# board.net
KiCad netlist of a schematic drawn in EAGLE
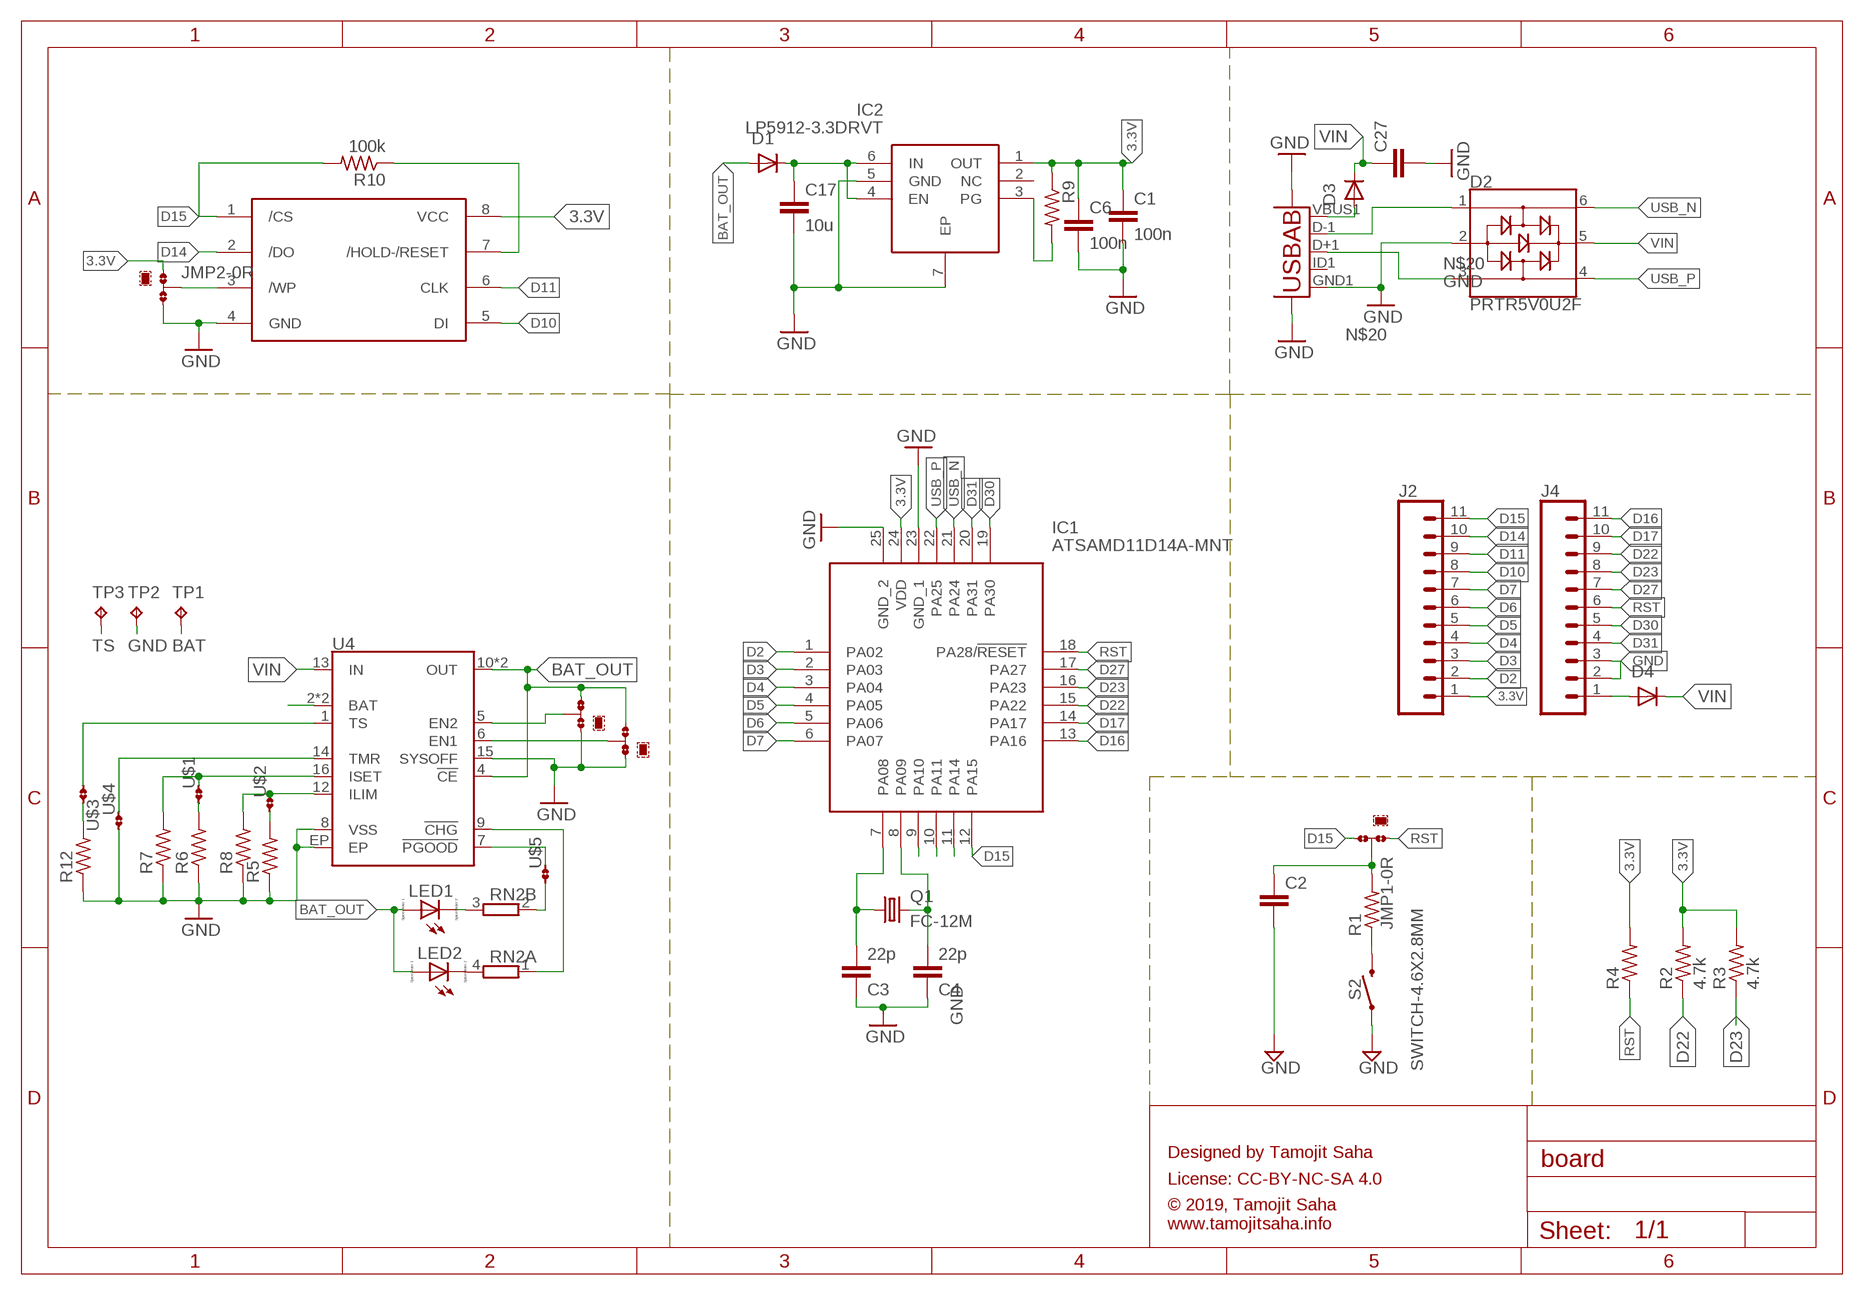
[diagram p0: schematic, sheet 1]

(export (version "E")
  (design (tool "Eeschema 10.0.6"))
  (components
    (comp (ref "C1")
      (value "100n")
      (footprint "eagle-import:C0402")
      (libsource (lib "eagle-import") (part "C-EUC0402"))
    )
    (comp (ref "C2")
      (value "C-EUC0402")
      (footprint "eagle-import:C0402")
      (libsource (lib "eagle-import") (part "C-EUC0402"))
    )
    (comp (ref "C3")
      (value "22p")
      (footprint "eagle-import:C0402")
      (libsource (lib "eagle-import") (part "C-EUC0402"))
    )
    (comp (ref "C4")
      (value "22p")
      (footprint "eagle-import:C0402")
      (libsource (lib "eagle-import") (part "C-EUC0402"))
    )
    (comp (ref "C6")
      (value "100n")
      (footprint "eagle-import:C0402")
      (libsource (lib "eagle-import") (part "C-EUC0402"))
    )
    (comp (ref "C17")
      (value "10u")
      (footprint "eagle-import:C0603")
      (libsource (lib "eagle-import") (part "C-EUC0603"))
    )
    (comp (ref "C27")
      (value "C-EUC0603")
      (footprint "eagle-import:C0603")
      (libsource (lib "eagle-import") (part "C-EUC0603"))
    )
    (comp (ref "D1")
      (value "PMEG1030")
      (footprint "eagle-import:SOD323(F)")
      (fields (field (name "MF") "NXP Semiconductors") (field (name "MP") "BAS21J"))
      (libsource (lib "eagle-import") (part "PMEG1030"))
    )
    (comp (ref "D2")
      (value "PRTR5V0U2F")
      (footprint "eagle-import:SOT886")
      (libsource (lib "eagle-import") (part "PRTR5V0U2F"))
    )
    (comp (ref "D3")
      (value "PMEG1030")
      (footprint "eagle-import:SOD323(F)")
      (fields (field (name "MF") "NXP Semiconductors") (field (name "MP") "BAS21J"))
      (libsource (lib "eagle-import") (part "PMEG1030"))
    )
    (comp (ref "D4")
      (value "PMEG1030")
      (footprint "eagle-import:SOD323(F)")
      (fields (field (name "MF") "NXP Semiconductors") (field (name "MP") "BAS21J"))
      (libsource (lib "eagle-import") (part "PMEG1030"))
    )
    (comp (ref "EEPROM1")
      (value "W25Q128JVPIQ")
      (footprint "eagle-import:SON127P600X500X80-9N")
      (libsource (lib "eagle-import") (part "W25Q128JVPIQ"))
    )
    (comp (ref "IC1")
      (value "ATSAMD11D14A-MNT")
      (footprint "eagle-import:QFN50P400X400X90-25N")
      (fields (field (name "MOUSER_PART_NUMBER") "556-ATSAMD11D14A-MNT"))
      (libsource (lib "eagle-import") (part "ATSAMD11D14A-MNT"))
    )
    (comp (ref "IC2")
      (value "LP5912-3.3DRVT")
      (footprint "eagle-import:WSON-6")
      (fields (field (name "MOUSER_PART_NUMBER") "595-LP5912-3.3DRVT"))
      (libsource (lib "eagle-import") (part "LP5912-3.3DRVT"))
    )
    (comp (ref "J2")
      (value "CONN_111X11_NO_SILK")
      (footprint "eagle-import:1X11_NO_SILK")
      (libsource (lib "eagle-import") (part "CONN_111X11_NO_SILK"))
    )
    (comp (ref "J4")
      (value "CONN_111X11_NO_SILK")
      (footprint "eagle-import:1X11_NO_SILK")
      (libsource (lib "eagle-import") (part "CONN_111X11_NO_SILK"))
    )
    (comp (ref "JMP1")
      (value "0R-JUMPA")
      (footprint "eagle-import:A0R-JMP")
      (libsource (lib "eagle-import") (part "0R-JUMPA"))
    )
    (comp (ref "JMP2")
      (value "0R-JUMPA")
      (footprint "eagle-import:A0R-JMP")
      (libsource (lib "eagle-import") (part "0R-JUMPA"))
    )
    (comp (ref "JMP3")
      (value "0R-JUMPA")
      (footprint "eagle-import:A0R-JMP")
      (libsource (lib "eagle-import") (part "0R-JUMPA"))
    )
    (comp (ref "JMP4")
      (value "0R-JUMPA")
      (footprint "eagle-import:A0R-JMP")
      (libsource (lib "eagle-import") (part "0R-JUMPA"))
    )
    (comp (ref "LED1")
      (value "LED_ESML0603")
      (footprint "eagle-import:LED_SML0603")
      (libsource (lib "eagle-import") (part "LED_ESML0603"))
    )
    (comp (ref "LED2")
      (value "LED_ESML0603")
      (footprint "eagle-import:LED_SML0603")
      (libsource (lib "eagle-import") (part "LED_ESML0603"))
    )
    (comp (ref "Q1")
      (value "FC-12M")
      (footprint "eagle-import:FC-12M")
      (libsource (lib "eagle-import") (part "FC-12M"))
    )
    (comp (ref "R1")
      (value "R-US_R0402")
      (footprint "eagle-import:R0402")
      (libsource (lib "eagle-import") (part "R-US_R0402"))
    )
    (comp (ref "R2")
      (value "4.7k")
      (footprint "eagle-import:R0402")
      (libsource (lib "eagle-import") (part "R-US_R0402"))
    )
    (comp (ref "R3")
      (value "4.7k")
      (footprint "eagle-import:R0402")
      (libsource (lib "eagle-import") (part "R-US_R0402"))
    )
    (comp (ref "R4")
      (value "R-US_R0402")
      (footprint "eagle-import:R0402")
      (libsource (lib "eagle-import") (part "R-US_R0402"))
    )
    (comp (ref "R5")
      (value "R-US_R0402")
      (footprint "eagle-import:R0402")
      (libsource (lib "eagle-import") (part "R-US_R0402"))
    )
    (comp (ref "R6")
      (value "R-US_R0402")
      (footprint "eagle-import:R0402")
      (libsource (lib "eagle-import") (part "R-US_R0402"))
    )
    (comp (ref "R7")
      (value "R-US_R0402")
      (footprint "eagle-import:R0402")
      (libsource (lib "eagle-import") (part "R-US_R0402"))
    )
    (comp (ref "R8")
      (value "R-US_R0402")
      (footprint "eagle-import:R0402")
      (libsource (lib "eagle-import") (part "R-US_R0402"))
    )
    (comp (ref "R9")
      (value "R-US_R0402")
      (footprint "eagle-import:R0402")
      (libsource (lib "eagle-import") (part "R-US_R0402"))
    )
    (comp (ref "R10")
      (value "100k")
      (footprint "eagle-import:R0402")
      (libsource (lib "eagle-import") (part "R-US_R0402"))
    )
    (comp (ref "R12")
      (value "R-US_R0402")
      (footprint "eagle-import:R0402")
      (libsource (lib "eagle-import") (part "R-US_R0402"))
    )
    (comp (ref "RN2")
      (value "2R-NEXB24V")
      (footprint "eagle-import:EXB24V")
      (libsource (lib "eagle-import") (part "2R-NEXB24V"))
    )
    (comp (ref "S2")
      (value "SWITCH-4.6X2.8MM")
      (footprint "eagle-import:TACTILE_SWITCH_SMD_4.6X2.8MM")
      (libsource (lib "eagle-import") (part "MOMENTARY-SWITCH-SPST-SMD-4.6X2.8MM"))
    )
    (comp (ref "TP1")
      (value "TPB1,27")
      (footprint "eagle-import:B1,27")
      (libsource (lib "eagle-import") (part "TPB1,27"))
    )
    (comp (ref "TP2")
      (value "TPB1,27")
      (footprint "eagle-import:B1,27")
      (libsource (lib "eagle-import") (part "TPB1,27"))
    )
    (comp (ref "TP3")
      (value "TPB1,27")
      (footprint "eagle-import:B1,27")
      (libsource (lib "eagle-import") (part "TPB1,27"))
    )
    (comp (ref "U$1")
      (value "JMP-2-NO-0402")
      (footprint "eagle-import:JMP-2-NO-0402")
      (libsource (lib "eagle-import") (part "JMP-2-NO-0402"))
    )
    (comp (ref "U$2")
      (value "JMP-2-NO-0402")
      (footprint "eagle-import:JMP-2-NO-0402")
      (libsource (lib "eagle-import") (part "JMP-2-NO-0402"))
    )
    (comp (ref "U$3")
      (value "JMP-2-NO-0402")
      (footprint "eagle-import:JMP-2-NO-0402")
      (libsource (lib "eagle-import") (part "JMP-2-NO-0402"))
    )
    (comp (ref "U$4")
      (value "JMP-2-NO-0402")
      (footprint "eagle-import:JMP-2-NO-0402")
      (libsource (lib "eagle-import") (part "JMP-2-NO-0402"))
    )
    (comp (ref "U$5")
      (value "JMP-2-NO-0402")
      (footprint "eagle-import:JMP-2-NO-0402")
      (libsource (lib "eagle-import") (part "JMP-2-NO-0402"))
    )
    (comp (ref "U3")
      (value "USB\"\"")
      (footprint "eagle-import:USB-MICRO-SMD")
      (libsource (lib "eagle-import") (part "USB{dblquote}{dblquote}"))
    )
    (comp (ref "U4")
      (value "BQ24075")
      (footprint "eagle-import:PVQFN-N16")
      (libsource (lib "eagle-import") (part "BQ24075"))
    )
  )
  (nets
    (net (code "1") (name "/BAT") (class "Default")
      (node (ref "TP1") (pin "TP") (pinfunction "TP_TP") (pintype "input"))
      (node (ref "U4") (pin "2") (pinfunction "BAT_2") (pintype "bidirectional"))
      (node (ref "U4") (pin "3") (pinfunction "BAT_3") (pintype "bidirectional"))
    )
    (net (code "2") (name "/N$20") (class "Default")
      (node (ref "D3") (pin "2") (pinfunction "A_2") (pintype "passive"))
      (node (ref "U3") (pin "VBUS1") (pinfunction "VBUS_VBUS1") (pintype "bidirectional"))
    )
    (net (code "3") (name "/TS") (class "Default")
      (node (ref "TP3") (pin "TP") (pinfunction "TP_TP") (pintype "input"))
      (node (ref "U$3") (pin "1") (pinfunction "1_1") (pintype "passive"))
      (node (ref "U4") (pin "1") (pinfunction "TS_1") (pintype "bidirectional"))
    )
    (net (code "4") (name "3.3V") (class "Default")
      (node (ref "C1") (pin "1") (pinfunction "1_1") (pintype "passive"))
      (node (ref "C6") (pin "1") (pinfunction "1_1") (pintype "passive"))
      (node (ref "EEPROM1") (pin "8") (pinfunction "VCC_8") (pintype "bidirectional"))
      (node (ref "IC1") (pin "24") (pinfunction "VDD_24") (pintype "bidirectional"))
      (node (ref "IC2") (pin "1") (pinfunction "OUT_1") (pintype "bidirectional"))
      (node (ref "J2") (pin "1") (pinfunction "1_1") (pintype "passive"))
      (node (ref "JMP2") (pin "1") (pinfunction "1_1") (pintype "passive"))
      (node (ref "R2") (pin "2") (pinfunction "2_2") (pintype "passive"))
      (node (ref "R3") (pin "2") (pinfunction "2_2") (pintype "passive"))
      (node (ref "R4") (pin "2") (pinfunction "2_2") (pintype "passive"))
      (node (ref "R9") (pin "1") (pinfunction "1_1") (pintype "passive"))
    )
    (net (code "5") (name "BAT_OUT") (class "Default")
      (node (ref "D1") (pin "2") (pinfunction "A_2") (pintype "passive"))
      (node (ref "JMP3") (pin "3") (pinfunction "3_3") (pintype "passive"))
      (node (ref "JMP4") (pin "3") (pinfunction "3_3") (pintype "passive"))
      (node (ref "LED1") (pin "A") (pinfunction "A_A") (pintype "passive"))
      (node (ref "LED2") (pin "A") (pinfunction "A_A") (pintype "passive"))
      (node (ref "U4") (pin "10") (pinfunction "OUT_10") (pintype "bidirectional"))
      (node (ref "U4") (pin "11") (pinfunction "OUT_11") (pintype "bidirectional"))
      (node (ref "U4") (pin "4") (pinfunction "~{CE}_4") (pintype "bidirectional"))
    )
    (net (code "6") (name "D2") (class "Default")
      (node (ref "IC1") (pin "1") (pinfunction "PA02_1") (pintype "bidirectional"))
      (node (ref "J2") (pin "2") (pinfunction "2_2") (pintype "passive"))
    )
    (net (code "7") (name "D3") (class "Default")
      (node (ref "IC1") (pin "2") (pinfunction "PA03_2") (pintype "bidirectional"))
      (node (ref "J2") (pin "3") (pinfunction "3_3") (pintype "passive"))
    )
    (net (code "8") (name "D4") (class "Default")
      (node (ref "IC1") (pin "3") (pinfunction "PA04_3") (pintype "bidirectional"))
      (node (ref "J2") (pin "4") (pinfunction "4_4") (pintype "passive"))
    )
    (net (code "9") (name "D5") (class "Default")
      (node (ref "IC1") (pin "4") (pinfunction "PA05_4") (pintype "bidirectional"))
      (node (ref "J2") (pin "5") (pinfunction "5_5") (pintype "passive"))
    )
    (net (code "10") (name "D6") (class "Default")
      (node (ref "IC1") (pin "5") (pinfunction "PA06_5") (pintype "bidirectional"))
      (node (ref "J2") (pin "6") (pinfunction "6_6") (pintype "passive"))
    )
    (net (code "11") (name "D7") (class "Default")
      (node (ref "IC1") (pin "6") (pinfunction "PA07_6") (pintype "bidirectional"))
      (node (ref "J2") (pin "7") (pinfunction "7_7") (pintype "passive"))
    )
    (net (code "12") (name "D10") (class "Default")
      (node (ref "EEPROM1") (pin "5") (pinfunction "DI_5") (pintype "bidirectional"))
      (node (ref "IC1") (pin "9") (pinfunction "PA10_9") (pintype "bidirectional"))
      (node (ref "J2") (pin "8") (pinfunction "8_8") (pintype "passive"))
    )
    (net (code "13") (name "D11") (class "Default")
      (node (ref "EEPROM1") (pin "6") (pinfunction "CLK_6") (pintype "bidirectional"))
      (node (ref "IC1") (pin "10") (pinfunction "PA11_10") (pintype "bidirectional"))
      (node (ref "J2") (pin "9") (pinfunction "9_9") (pintype "passive"))
    )
    (net (code "14") (name "D14") (class "Default")
      (node (ref "EEPROM1") (pin "2") (pinfunction "/DO_2") (pintype "bidirectional"))
      (node (ref "IC1") (pin "11") (pinfunction "PA14_11") (pintype "bidirectional"))
      (node (ref "J2") (pin "10") (pinfunction "10_10") (pintype "passive"))
    )
    (net (code "15") (name "D15") (class "Default")
      (node (ref "EEPROM1") (pin "1") (pinfunction "/CS_1") (pintype "bidirectional"))
      (node (ref "IC1") (pin "12") (pinfunction "PA15_12") (pintype "bidirectional"))
      (node (ref "J2") (pin "11") (pinfunction "11_11") (pintype "passive"))
      (node (ref "JMP1") (pin "3") (pinfunction "3_3") (pintype "passive"))
      (node (ref "R10") (pin "2") (pinfunction "2_2") (pintype "passive"))
    )
    (net (code "16") (name "D16") (class "Default")
      (node (ref "IC1") (pin "13") (pinfunction "PA16_13") (pintype "bidirectional"))
      (node (ref "J4") (pin "11") (pinfunction "11_11") (pintype "passive"))
    )
    (net (code "17") (name "D17") (class "Default")
      (node (ref "IC1") (pin "14") (pinfunction "PA17_14") (pintype "bidirectional"))
      (node (ref "J4") (pin "10") (pinfunction "10_10") (pintype "passive"))
    )
    (net (code "18") (name "D22") (class "Default")
      (node (ref "IC1") (pin "15") (pinfunction "PA22_15") (pintype "bidirectional"))
      (node (ref "J4") (pin "9") (pinfunction "9_9") (pintype "passive"))
      (node (ref "R2") (pin "1") (pinfunction "1_1") (pintype "passive"))
    )
    (net (code "19") (name "D23") (class "Default")
      (node (ref "IC1") (pin "16") (pinfunction "PA23_16") (pintype "bidirectional"))
      (node (ref "J4") (pin "8") (pinfunction "8_8") (pintype "passive"))
      (node (ref "R3") (pin "1") (pinfunction "1_1") (pintype "passive"))
    )
    (net (code "20") (name "D27") (class "Default")
      (node (ref "IC1") (pin "17") (pinfunction "PA27_17") (pintype "bidirectional"))
      (node (ref "J4") (pin "7") (pinfunction "7_7") (pintype "passive"))
    )
    (net (code "21") (name "D30") (class "Default")
      (node (ref "IC1") (pin "19") (pinfunction "PA30_19") (pintype "bidirectional"))
      (node (ref "J4") (pin "5") (pinfunction "5_5") (pintype "passive"))
    )
    (net (code "22") (name "D31") (class "Default")
      (node (ref "IC1") (pin "20") (pinfunction "PA31_20") (pintype "bidirectional"))
      (node (ref "J4") (pin "4") (pinfunction "4_4") (pintype "passive"))
    )
    (net (code "23") (name "GND") (class "Default")
      (node (ref "C1") (pin "2") (pinfunction "2_2") (pintype "passive"))
      (node (ref "C17") (pin "2") (pinfunction "2_2") (pintype "passive"))
      (node (ref "C2") (pin "2") (pinfunction "2_2") (pintype "passive"))
      (node (ref "C27") (pin "2") (pinfunction "2_2") (pintype "passive"))
      (node (ref "C3") (pin "1") (pinfunction "1_1") (pintype "passive"))
      (node (ref "C4") (pin "1") (pinfunction "1_1") (pintype "passive"))
      (node (ref "C6") (pin "2") (pinfunction "2_2") (pintype "passive"))
      (node (ref "D2") (pin "2") (pinfunction "2_2") (pintype "bidirectional"))
      (node (ref "EEPROM1") (pin "4") (pinfunction "GND_4") (pintype "bidirectional"))
      (node (ref "IC1") (pin "23") (pinfunction "GND_1_23") (pintype "power_in"))
      (node (ref "IC1") (pin "25") (pinfunction "GND_2_25") (pintype "power_in"))
      (node (ref "IC2") (pin "5") (pinfunction "GND_5") (pintype "bidirectional"))
      (node (ref "IC2") (pin "7") (pinfunction "EP_7") (pintype "bidirectional"))
      (node (ref "J4") (pin "2") (pinfunction "2_2") (pintype "passive"))
      (node (ref "J4") (pin "3") (pinfunction "3_3") (pintype "passive"))
      (node (ref "JMP2") (pin "3") (pinfunction "3_3") (pintype "passive"))
      (node (ref "JMP3") (pin "1") (pinfunction "1_1") (pintype "passive"))
      (node (ref "JMP4") (pin "1") (pinfunction "1_1") (pintype "passive"))
      (node (ref "R12") (pin "1") (pinfunction "1_1") (pintype "passive"))
      (node (ref "R5") (pin "1") (pinfunction "1_1") (pintype "passive"))
      (node (ref "R6") (pin "1") (pinfunction "1_1") (pintype "passive"))
      (node (ref "R7") (pin "1") (pinfunction "1_1") (pintype "passive"))
      (node (ref "R8") (pin "1") (pinfunction "1_1") (pintype "passive"))
      (node (ref "S2") (pin "1") (pinfunction "1_1") (pintype "passive"))
      (node (ref "S2") (pin "2") (pinfunction "1_2") (pintype "passive"))
      (node (ref "TP2") (pin "TP") (pinfunction "TP_TP") (pintype "input"))
      (node (ref "U$4") (pin "1") (pinfunction "1_1") (pintype "passive"))
      (node (ref "U3") (pin "GND1") (pinfunction "GND_GND1") (pintype "bidirectional"))
      (node (ref "U3") (pin "SH1") (pinfunction "P$1_SH1") (pintype "bidirectional"))
      (node (ref "U3") (pin "SH2") (pinfunction "P$2_SH2") (pintype "bidirectional"))
      (node (ref "U4") (pin "15") (pinfunction "SYSOFF_15") (pintype "bidirectional"))
      (node (ref "U4") (pin "8") (pinfunction "VSS_8") (pintype "bidirectional"))
      (node (ref "U4") (pin "EP") (pinfunction "EP_EP") (pintype "bidirectional"))
    )
    (net (code "24") (name "Net-(C2-Pad1)") (class "Default")
      (node (ref "C2") (pin "1") (pinfunction "1_1") (pintype "passive"))
      (node (ref "JMP1") (pin "2") (pinfunction "2_2") (pintype "passive"))
      (node (ref "R1") (pin "2") (pinfunction "2_2") (pintype "passive"))
    )
    (net (code "25") (name "Net-(D1-K)") (class "Default")
      (node (ref "C17") (pin "1") (pinfunction "1_1") (pintype "passive"))
      (node (ref "D1") (pin "1") (pinfunction "K_1") (pintype "passive"))
      (node (ref "IC2") (pin "4") (pinfunction "EN_4") (pintype "bidirectional"))
      (node (ref "IC2") (pin "6") (pinfunction "IN_6") (pintype "bidirectional"))
    )
    (net (code "26") (name "Net-(D4-A)") (class "Default")
      (node (ref "D4") (pin "2") (pinfunction "A_2") (pintype "passive"))
      (node (ref "J4") (pin "1") (pinfunction "1_1") (pintype "passive"))
    )
    (net (code "27") (name "Net-(EEPROM1-{slash}HOLD-{slash}RESET)") (class "Default")
      (node (ref "EEPROM1") (pin "7") (pinfunction "/HOLD-/RESET_7") (pintype "bidirectional"))
      (node (ref "R10") (pin "1") (pinfunction "1_1") (pintype "passive"))
    )
    (net (code "28") (name "Net-(EEPROM1-{slash}WP)") (class "Default")
      (node (ref "EEPROM1") (pin "3") (pinfunction "/WP_3") (pintype "bidirectional"))
      (node (ref "JMP2") (pin "2") (pinfunction "2_2") (pintype "passive"))
    )
    (net (code "29") (name "Net-(IC1-PA08)") (class "Default")
      (node (ref "C3") (pin "2") (pinfunction "2_2") (pintype "passive"))
      (node (ref "IC1") (pin "7") (pinfunction "PA08_7") (pintype "bidirectional"))
      (node (ref "Q1") (pin "1") (pinfunction "1_1") (pintype "passive"))
    )
    (net (code "30") (name "Net-(IC1-PA09)") (class "Default")
      (node (ref "C4") (pin "2") (pinfunction "2_2") (pintype "passive"))
      (node (ref "IC1") (pin "8") (pinfunction "PA09_8") (pintype "bidirectional"))
      (node (ref "Q1") (pin "2") (pinfunction "2_2") (pintype "passive"))
    )
    (net (code "31") (name "Net-(IC2-PG)") (class "Default")
      (node (ref "IC2") (pin "3") (pinfunction "PG_3") (pintype "bidirectional"))
      (node (ref "R9") (pin "2") (pinfunction "2_2") (pintype "passive"))
    )
    (net (code "32") (name "Net-(R1-Pad1)") (class "Default")
      (node (ref "R1") (pin "1") (pinfunction "1_1") (pintype "passive"))
      (node (ref "S2") (pin "3") (pinfunction "2_3") (pintype "passive"))
      (node (ref "S2") (pin "4") (pinfunction "2_4") (pintype "passive"))
    )
    (net (code "33") (name "Net-(R5-Pad2)") (class "Default")
      (node (ref "R5") (pin "2") (pinfunction "2_2") (pintype "passive"))
      (node (ref "U$2") (pin "1") (pinfunction "1_1") (pintype "passive"))
    )
    (net (code "34") (name "Net-(R6-Pad2)") (class "Default")
      (node (ref "R6") (pin "2") (pinfunction "2_2") (pintype "passive"))
      (node (ref "U$1") (pin "1") (pinfunction "1_1") (pintype "passive"))
    )
    (net (code "35") (name "Net-(R12-Pad2)") (class "Default")
      (node (ref "R12") (pin "2") (pinfunction "2_2") (pintype "passive"))
      (node (ref "U$3") (pin "2") (pinfunction "2_2") (pintype "passive"))
    )
    (net (code "36") (name "Net-(RN2A-2)") (class "Default")
      (node (ref "LED2") (pin "C") (pinfunction "C_C") (pintype "passive"))
      (node (ref "RN2") (pin "4") (pinfunction "2_4") (pintype "passive"))
    )
    (net (code "37") (name "Net-(RN2B-1)") (class "Default")
      (node (ref "RN2") (pin "2") (pinfunction "1_2") (pintype "passive"))
      (node (ref "U$5") (pin "1") (pinfunction "1_1") (pintype "passive"))
    )
    (net (code "38") (name "Net-(RN2B-2)") (class "Default")
      (node (ref "LED1") (pin "C") (pinfunction "C_C") (pintype "passive"))
      (node (ref "RN2") (pin "3") (pinfunction "2_3") (pintype "passive"))
    )
    (net (code "39") (name "Net-(U3-D+)") (class "Default")
      (node (ref "D2") (pin "3") (pinfunction "3_3") (pintype "bidirectional"))
      (node (ref "U3") (pin "D+1") (pinfunction "D+_D+1") (pintype "bidirectional"))
    )
    (net (code "40") (name "Net-(U3-D-)") (class "Default")
      (node (ref "D2") (pin "1") (pinfunction "1_1") (pintype "bidirectional"))
      (node (ref "U3") (pin "D-1") (pinfunction "D-_D-1") (pintype "bidirectional"))
    )
    (net (code "41") (name "Net-(U4-EN1)") (class "Default")
      (node (ref "JMP3") (pin "2") (pinfunction "2_2") (pintype "passive"))
      (node (ref "U4") (pin "6") (pinfunction "EN1_6") (pintype "bidirectional"))
    )
    (net (code "42") (name "Net-(U4-EN2)") (class "Default")
      (node (ref "JMP4") (pin "2") (pinfunction "2_2") (pintype "passive"))
      (node (ref "U4") (pin "5") (pinfunction "EN2_5") (pintype "bidirectional"))
    )
    (net (code "43") (name "Net-(U4-ILIM)") (class "Default")
      (node (ref "R8") (pin "2") (pinfunction "2_2") (pintype "passive"))
      (node (ref "U$2") (pin "2") (pinfunction "2_2") (pintype "passive"))
      (node (ref "U4") (pin "12") (pinfunction "ILIM_12") (pintype "bidirectional"))
    )
    (net (code "44") (name "Net-(U4-ISET)") (class "Default")
      (node (ref "R7") (pin "2") (pinfunction "2_2") (pintype "passive"))
      (node (ref "U$1") (pin "2") (pinfunction "2_2") (pintype "passive"))
      (node (ref "U4") (pin "16") (pinfunction "ISET_16") (pintype "bidirectional"))
    )
    (net (code "45") (name "Net-(U4-TMR)") (class "Default")
      (node (ref "U$4") (pin "2") (pinfunction "2_2") (pintype "passive"))
      (node (ref "U4") (pin "14") (pinfunction "TMR_14") (pintype "bidirectional"))
    )
    (net (code "46") (name "Net-(U4-~{CHG})") (class "Default")
      (node (ref "RN2") (pin "1") (pinfunction "1_1") (pintype "passive"))
      (node (ref "U4") (pin "9") (pinfunction "~{CHG}_9") (pintype "bidirectional"))
    )
    (net (code "47") (name "Net-(U4-~{PGOOD})") (class "Default")
      (node (ref "U$5") (pin "2") (pinfunction "2_2") (pintype "passive"))
      (node (ref "U4") (pin "7") (pinfunction "~{PGOOD}_7") (pintype "bidirectional"))
    )
    (net (code "48") (name "RST") (class "Default")
      (node (ref "IC1") (pin "18") (pinfunction "PA28/~{RESET}_18") (pintype "bidirectional"))
      (node (ref "J4") (pin "6") (pinfunction "6_6") (pintype "passive"))
      (node (ref "JMP1") (pin "1") (pinfunction "1_1") (pintype "passive"))
      (node (ref "R4") (pin "1") (pinfunction "1_1") (pintype "passive"))
    )
    (net (code "49") (name "USB_N") (class "Default")
      (node (ref "D2") (pin "6") (pinfunction "6_6") (pintype "bidirectional"))
      (node (ref "IC1") (pin "21") (pinfunction "PA24_21") (pintype "bidirectional"))
    )
    (net (code "50") (name "USB_P") (class "Default")
      (node (ref "D2") (pin "4") (pinfunction "4_4") (pintype "bidirectional"))
      (node (ref "IC1") (pin "22") (pinfunction "PA25_22") (pintype "bidirectional"))
    )
    (net (code "51") (name "VIN") (class "Default")
      (node (ref "C27") (pin "1") (pinfunction "1_1") (pintype "passive"))
      (node (ref "D2") (pin "5") (pinfunction "5_5") (pintype "bidirectional"))
      (node (ref "D3") (pin "1") (pinfunction "K_1") (pintype "passive"))
      (node (ref "D4") (pin "1") (pinfunction "K_1") (pintype "passive"))
      (node (ref "U4") (pin "13") (pinfunction "IN_13") (pintype "bidirectional"))
    )
    (net (code "52") (name "unconnected-(IC2-NC-Pad2)") (class "Default")
      (node (ref "IC2") (pin "2") (pinfunction "NC_2") (pintype "no_connect"))
    )
    (net (code "53") (name "unconnected-(U3-USBID-PadID1)") (class "Default")
      (node (ref "U3") (pin "ID1") (pinfunction "USBID_ID1") (pintype "bidirectional"))
    )
  )
)
